# PR5006.net
KiCad netlist of a schematic drawn in EAGLE
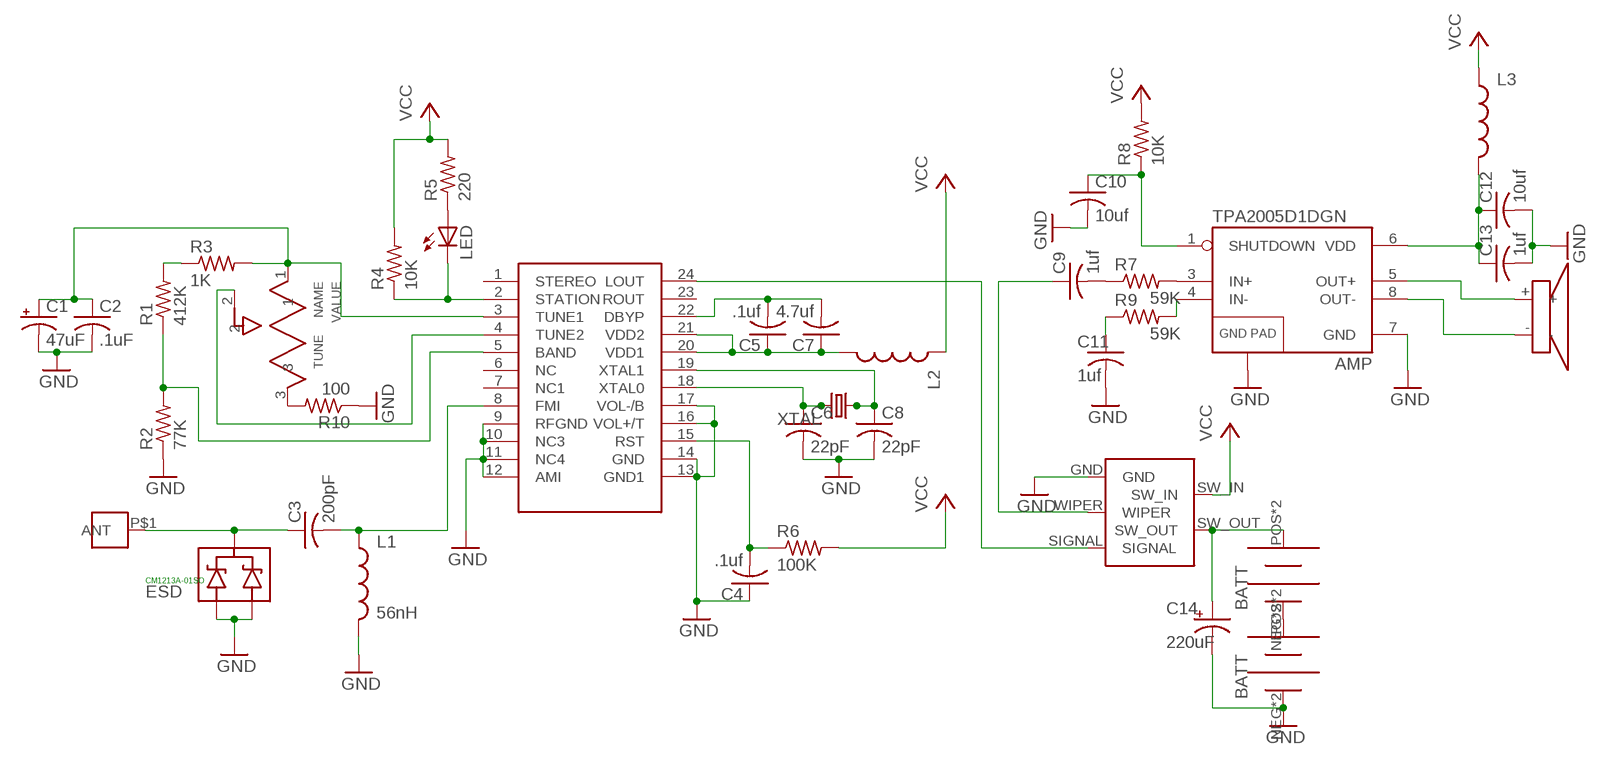
[diagram p0: schematic, sheet 1]

(export (version "E")
  (design (tool "Eeschema 10.0.6"))
  (components
    (comp (ref "AMP")
      (value "TPA2005D1DGN")
      (footprint "eagle-import:POWER-SOP8")
      (libsource (lib "eagle-import") (part "TPA2005D1DGN"))
    )
    (comp (ref "ANT")
      (value "M3_SCREW_POST")
      (footprint "eagle-import:M3_SCREW_POST")
      (libsource (lib "eagle-import") (part "M3_SCREW_POST"))
    )
    (comp (ref "C1")
      (value "47uF")
      (footprint "eagle-import:E2-5")
      (libsource (lib "eagle-import") (part "CPOL-USE2-5"))
    )
    (comp (ref "C2")
      (value ".1uF")
      (footprint "eagle-import:C0603")
      (libsource (lib "eagle-import") (part "C-USC0603"))
    )
    (comp (ref "C3")
      (value "200pF")
      (footprint "eagle-import:C0603")
      (libsource (lib "eagle-import") (part "C-USC0603"))
    )
    (comp (ref "C4")
      (value ".1uf")
      (footprint "eagle-import:C0603")
      (libsource (lib "eagle-import") (part "C-USC0603"))
    )
    (comp (ref "C5")
      (value ".1uf")
      (footprint "eagle-import:C0603")
      (libsource (lib "eagle-import") (part "C-USC0603"))
    )
    (comp (ref "C6")
      (value "22pF")
      (footprint "eagle-import:C0603")
      (libsource (lib "eagle-import") (part "C-USC0603"))
    )
    (comp (ref "C7")
      (value "4.7uf")
      (footprint "eagle-import:C0603")
      (libsource (lib "eagle-import") (part "C-USC0603"))
    )
    (comp (ref "C8")
      (value "22pF")
      (footprint "eagle-import:C0603")
      (libsource (lib "eagle-import") (part "C-USC0603"))
    )
    (comp (ref "C9")
      (value "1uf")
      (footprint "eagle-import:C0603")
      (libsource (lib "eagle-import") (part "C-USC0603"))
    )
    (comp (ref "C10")
      (value "10uf")
      (footprint "eagle-import:C0603")
      (libsource (lib "eagle-import") (part "C-USC0603"))
    )
    (comp (ref "C11")
      (value "1uf")
      (footprint "eagle-import:C0603")
      (libsource (lib "eagle-import") (part "C-USC0603"))
    )
    (comp (ref "C12")
      (value "10uf")
      (footprint "eagle-import:C0603")
      (libsource (lib "eagle-import") (part "C-USC0603"))
    )
    (comp (ref "C13")
      (value "1uf")
      (footprint "eagle-import:C0603")
      (libsource (lib "eagle-import") (part "C-USC0603"))
    )
    (comp (ref "C14")
      (value "220uF")
      (footprint "eagle-import:E2,5-5")
      (libsource (lib "eagle-import") (part "CPOL-USE2.5-5"))
    )
    (comp (ref "ESD")
      (value "CM1213A-01SO")
      (footprint "eagle-import:SOT23-3")
      (libsource (lib "eagle-import") (part "MMBZ27VCLT1"))
    )
    (comp (ref "L1")
      (value "56nH")
      (footprint "eagle-import:0603")
      (libsource (lib "eagle-import") (part "INDUCTOR0603"))
    )
    (comp (ref "L2")
      (value "INDUCTOR0603")
      (footprint "eagle-import:0603")
      (libsource (lib "eagle-import") (part "INDUCTOR0603"))
    )
    (comp (ref "L3")
      (value "INDUCTOR0603")
      (footprint "eagle-import:0603")
      (libsource (lib "eagle-import") (part "INDUCTOR0603"))
    )
    (comp (ref "LED")
      (value "LEDCHIP-LED0603")
      (footprint "eagle-import:CHIP-LED0603")
      (libsource (lib "eagle-import") (part "LEDCHIP-LED0603"))
    )
    (comp (ref "R1")
      (value "412K")
      (footprint "eagle-import:R0603")
      (libsource (lib "eagle-import") (part "R-US_R0603"))
    )
    (comp (ref "R2")
      (value "77K")
      (footprint "eagle-import:R0603")
      (libsource (lib "eagle-import") (part "R-US_R0603"))
    )
    (comp (ref "R3")
      (value "1K")
      (footprint "eagle-import:R0603")
      (libsource (lib "eagle-import") (part "R-US_R0603"))
    )
    (comp (ref "R4")
      (value "10K")
      (footprint "eagle-import:R0603")
      (libsource (lib "eagle-import") (part "R-US_R0603"))
    )
    (comp (ref "R5")
      (value "220")
      (footprint "eagle-import:R0603")
      (libsource (lib "eagle-import") (part "R-US_R0603"))
    )
    (comp (ref "R6")
      (value "100K")
      (footprint "eagle-import:R0603")
      (libsource (lib "eagle-import") (part "R-US_R0603"))
    )
    (comp (ref "R7")
      (value "59K")
      (footprint "eagle-import:R0603")
      (libsource (lib "eagle-import") (part "R-US_R0603"))
    )
    (comp (ref "R8")
      (value "10K")
      (footprint "eagle-import:R0603")
      (libsource (lib "eagle-import") (part "R-US_R0603"))
    )
    (comp (ref "R9")
      (value "59K")
      (footprint "eagle-import:R0603")
      (libsource (lib "eagle-import") (part "R-US_R0603"))
    )
    (comp (ref "R10")
      (value "100")
      (footprint "eagle-import:R0603")
      (libsource (lib "eagle-import") (part "R-US_R0603"))
    )
    (comp (ref "SI4831")
      (value "SI4831-SSOP-24")
      (footprint "eagle-import:SI4831-SSOP-24")
      (libsource (lib "eagle-import") (part "SI4831-SSOP-24"))
    )
    (comp (ref "TUNE")
      (value "TUNE")
      (footprint "eagle-import:64XR_BOURNS_TRIMPOT")
      (libsource (lib "eagle-import") (part "64XR_BOURNS_TRIMPOT"))
    )
    (comp (ref "U$1")
      (value "BK-92_MPD_AA_BATT_CLIP")
      (footprint "eagle-import:BK-92_MPD_AA_BATT_CLIP")
      (libsource (lib "eagle-import") (part "BK-92_MPD_AA_BATT_CLIP"))
    )
    (comp (ref "U$2")
      (value "BK-92_MPD_AA_BATT_CLIP")
      (footprint "eagle-import:BK-92_MPD_AA_BATT_CLIP")
      (libsource (lib "eagle-import") (part "BK-92_MPD_AA_BATT_CLIP"))
    )
    (comp (ref "U$3")
      (value "CE32A_DAYTON_SPKR")
      (footprint "eagle-import:CE32A_DAYTON_SPKR")
      (libsource (lib "eagle-import") (part "CE32A_DAYTON_SPKR"))
    )
    (comp (ref "U$5")
      (value "P170_BOURNS_POT_SW")
      (footprint "eagle-import:P170_BOURNS_POT_SW")
      (libsource (lib "eagle-import") (part "P170_BOURNS_POT_SW"))
    )
    (comp (ref "XTAL")
      (value "CRYSTAL32-SMD")
      (footprint "eagle-import:CRYSTAL-32KHZ-SMD")
      (libsource (lib "eagle-import") (part "CRYSTAL32-SMD"))
    )
  )
  (nets
    (net (code "1") (name "GND") (class "Default")
      (node (ref "AMP") (pin "7") (pinfunction "GND_7") (pintype "power_in"))
      (node (ref "AMP") (pin "9") (pinfunction "GND_9") (pintype "power_in"))
      (node (ref "C1") (pin "-") (pinfunction "-_-") (pintype "passive"))
      (node (ref "C10") (pin "2") (pinfunction "2_2") (pintype "passive"))
      (node (ref "C11") (pin "2") (pinfunction "2_2") (pintype "passive"))
      (node (ref "C12") (pin "2") (pinfunction "2_2") (pintype "passive"))
      (node (ref "C13") (pin "2") (pinfunction "2_2") (pintype "passive"))
      (node (ref "C14") (pin "-") (pinfunction "-_-") (pintype "passive"))
      (node (ref "C2") (pin "2") (pinfunction "2_2") (pintype "passive"))
      (node (ref "C4") (pin "1") (pinfunction "1_1") (pintype "passive"))
      (node (ref "C6") (pin "2") (pinfunction "2_2") (pintype "passive"))
      (node (ref "C8") (pin "2") (pinfunction "2_2") (pintype "passive"))
      (node (ref "ESD") (pin "1") (pinfunction "A1_1") (pintype "passive"))
      (node (ref "ESD") (pin "2") (pinfunction "A2_2") (pintype "passive"))
      (node (ref "L1") (pin "2") (pinfunction "2_2") (pintype "passive"))
      (node (ref "R10") (pin "1") (pinfunction "1_1") (pintype "passive"))
      (node (ref "R2") (pin "1") (pinfunction "1_1") (pintype "passive"))
      (node (ref "SI4831") (pin "10") (pinfunction "NC3_10") (pintype "bidirectional"))
      (node (ref "SI4831") (pin "11") (pinfunction "NC4_11") (pintype "bidirectional"))
      (node (ref "SI4831") (pin "12") (pinfunction "AMI_12") (pintype "bidirectional"))
      (node (ref "SI4831") (pin "13") (pinfunction "GND1_13") (pintype "bidirectional"))
      (node (ref "SI4831") (pin "14") (pinfunction "GND_14") (pintype "bidirectional"))
      (node (ref "SI4831") (pin "16") (pinfunction "VOL+/T_16") (pintype "bidirectional"))
      (node (ref "SI4831") (pin "17") (pinfunction "VOL-/B_17") (pintype "bidirectional"))
      (node (ref "SI4831") (pin "9") (pinfunction "RFGND_9") (pintype "bidirectional"))
      (node (ref "U$2") (pin "NEG") (pinfunction "NEG_NEG") (pintype "bidirectional"))
      (node (ref "U$2") (pin "NEG@2") (pinfunction "NEG_NEG@2") (pintype "bidirectional"))
      (node (ref "U$5") (pin "GND") (pinfunction "GND_GND") (pintype "bidirectional"))
    )
    (net (code "2") (name "Net-(AMP-IN+)") (class "Default")
      (node (ref "AMP") (pin "3") (pinfunction "IN+_3") (pintype "bidirectional"))
      (node (ref "R7") (pin "2") (pinfunction "2_2") (pintype "passive"))
    )
    (net (code "3") (name "Net-(AMP-IN-)") (class "Default")
      (node (ref "AMP") (pin "4") (pinfunction "IN-_4") (pintype "bidirectional"))
      (node (ref "R9") (pin "2") (pinfunction "2_2") (pintype "passive"))
    )
    (net (code "4") (name "Net-(AMP-OUT+)") (class "Default")
      (node (ref "AMP") (pin "5") (pinfunction "OUT+_5") (pintype "bidirectional"))
      (node (ref "U$3") (pin "+") (pinfunction "+_+") (pintype "bidirectional"))
    )
    (net (code "5") (name "Net-(AMP-OUT-)") (class "Default")
      (node (ref "AMP") (pin "8") (pinfunction "OUT-_8") (pintype "bidirectional"))
      (node (ref "U$3") (pin "-") (pinfunction "-_-") (pintype "bidirectional"))
    )
    (net (code "6") (name "Net-(AMP-SHUTDOWN)") (class "Default")
      (node (ref "AMP") (pin "1") (pinfunction "SHUTDOWN_1") (pintype "input"))
      (node (ref "C10") (pin "1") (pinfunction "1_1") (pintype "passive"))
      (node (ref "R8") (pin "1") (pinfunction "1_1") (pintype "passive"))
    )
    (net (code "7") (name "Net-(AMP-VDD)") (class "Default")
      (node (ref "AMP") (pin "6") (pinfunction "VDD_6") (pintype "power_in"))
      (node (ref "C12") (pin "1") (pinfunction "1_1") (pintype "passive"))
      (node (ref "C13") (pin "1") (pinfunction "1_1") (pintype "passive"))
      (node (ref "L3") (pin "2") (pinfunction "2_2") (pintype "passive"))
    )
    (net (code "8") (name "Net-(ANT-ANT)") (class "Default")
      (node (ref "ANT") (pin "P$1") (pinfunction "ANT_P$1") (pintype "bidirectional"))
      (node (ref "C3") (pin "1") (pinfunction "1_1") (pintype "passive"))
      (node (ref "ESD") (pin "3") (pinfunction "C_3") (pintype "passive"))
    )
    (net (code "9") (name "Net-(C9-Pad1)") (class "Default")
      (node (ref "C9") (pin "1") (pinfunction "1_1") (pintype "passive"))
      (node (ref "U$5") (pin "WIPER") (pinfunction "WIPER_WIPER") (pintype "bidirectional"))
    )
    (net (code "10") (name "Net-(C9-Pad2)") (class "Default")
      (node (ref "C9") (pin "2") (pinfunction "2_2") (pintype "passive"))
      (node (ref "R7") (pin "1") (pinfunction "1_1") (pintype "passive"))
    )
    (net (code "11") (name "Net-(C11-Pad1)") (class "Default")
      (node (ref "C11") (pin "1") (pinfunction "1_1") (pintype "passive"))
      (node (ref "R9") (pin "1") (pinfunction "1_1") (pintype "passive"))
    )
    (net (code "12") (name "Net-(C14-Pad+)") (class "Default")
      (node (ref "C14") (pin "+") (pinfunction "+_+") (pintype "passive"))
      (node (ref "U$1") (pin "POS") (pinfunction "POS_POS") (pintype "bidirectional"))
      (node (ref "U$1") (pin "POS@2") (pinfunction "POS_POS@2") (pintype "bidirectional"))
      (node (ref "U$5") (pin "SW_OUT") (pinfunction "SW_OUT_SW_OUT") (pintype "bidirectional"))
    )
    (net (code "13") (name "Net-(LED-PadA)") (class "Default")
      (node (ref "LED") (pin "A") (pinfunction "A_A") (pintype "passive"))
      (node (ref "R5") (pin "1") (pinfunction "1_1") (pintype "passive"))
    )
    (net (code "14") (name "Net-(R1-Pad2)") (class "Default")
      (node (ref "R1") (pin "2") (pinfunction "2_2") (pintype "passive"))
      (node (ref "R3") (pin "1") (pinfunction "1_1") (pintype "passive"))
    )
    (net (code "15") (name "Net-(R10-Pad2)") (class "Default")
      (node (ref "R10") (pin "2") (pinfunction "2_2") (pintype "passive"))
      (node (ref "TUNE") (pin "3") (pinfunction "3_3") (pintype "bidirectional"))
    )
    (net (code "16") (name "Net-(SI4831-BAND)") (class "Default")
      (node (ref "R1") (pin "1") (pinfunction "1_1") (pintype "passive"))
      (node (ref "R2") (pin "2") (pinfunction "2_2") (pintype "passive"))
      (node (ref "SI4831") (pin "5") (pinfunction "BAND_5") (pintype "bidirectional"))
    )
    (net (code "17") (name "Net-(SI4831-DBYP)") (class "Default")
      (node (ref "C5") (pin "2") (pinfunction "2_2") (pintype "passive"))
      (node (ref "C7") (pin "2") (pinfunction "2_2") (pintype "passive"))
      (node (ref "SI4831") (pin "22") (pinfunction "DBYP_22") (pintype "bidirectional"))
    )
    (net (code "18") (name "Net-(SI4831-FMI)") (class "Default")
      (node (ref "C3") (pin "2") (pinfunction "2_2") (pintype "passive"))
      (node (ref "L1") (pin "1") (pinfunction "1_1") (pintype "passive"))
      (node (ref "SI4831") (pin "8") (pinfunction "FMI_8") (pintype "bidirectional"))
    )
    (net (code "19") (name "Net-(SI4831-LOUT)") (class "Default")
      (node (ref "SI4831") (pin "24") (pinfunction "LOUT_24") (pintype "bidirectional"))
      (node (ref "U$5") (pin "SIGNAL") (pinfunction "SIGNAL_SIGNAL") (pintype "bidirectional"))
    )
    (net (code "20") (name "Net-(SI4831-RST)") (class "Default")
      (node (ref "C4") (pin "2") (pinfunction "2_2") (pintype "passive"))
      (node (ref "R6") (pin "1") (pinfunction "1_1") (pintype "passive"))
      (node (ref "SI4831") (pin "15") (pinfunction "RST_15") (pintype "bidirectional"))
    )
    (net (code "21") (name "Net-(SI4831-STATION)") (class "Default")
      (node (ref "LED") (pin "C") (pinfunction "C_C") (pintype "passive"))
      (node (ref "R4") (pin "1") (pinfunction "1_1") (pintype "passive"))
      (node (ref "SI4831") (pin "2") (pinfunction "STATION_2") (pintype "bidirectional"))
    )
    (net (code "22") (name "Net-(SI4831-TUNE1)") (class "Default")
      (node (ref "C1") (pin "+") (pinfunction "+_+") (pintype "passive"))
      (node (ref "C2") (pin "1") (pinfunction "1_1") (pintype "passive"))
      (node (ref "R3") (pin "2") (pinfunction "2_2") (pintype "passive"))
      (node (ref "SI4831") (pin "3") (pinfunction "TUNE1_3") (pintype "bidirectional"))
      (node (ref "TUNE") (pin "1") (pinfunction "1_1") (pintype "bidirectional"))
    )
    (net (code "23") (name "Net-(SI4831-TUNE2)") (class "Default")
      (node (ref "SI4831") (pin "4") (pinfunction "TUNE2_4") (pintype "bidirectional"))
      (node (ref "TUNE") (pin "2") (pinfunction "2_2") (pintype "bidirectional"))
    )
    (net (code "24") (name "Net-(SI4831-VDD1)") (class "Default")
      (node (ref "C5") (pin "1") (pinfunction "1_1") (pintype "passive"))
      (node (ref "C7") (pin "1") (pinfunction "1_1") (pintype "passive"))
      (node (ref "L2") (pin "2") (pinfunction "2_2") (pintype "passive"))
      (node (ref "SI4831") (pin "20") (pinfunction "VDD1_20") (pintype "bidirectional"))
      (node (ref "SI4831") (pin "21") (pinfunction "VDD2_21") (pintype "bidirectional"))
    )
    (net (code "25") (name "Net-(SI4831-XTAL0)") (class "Default")
      (node (ref "C6") (pin "1") (pinfunction "1_1") (pintype "passive"))
      (node (ref "SI4831") (pin "18") (pinfunction "XTAL0_18") (pintype "bidirectional"))
      (node (ref "XTAL") (pin "X2") (pinfunction "2_X2") (pintype "passive"))
    )
    (net (code "26") (name "Net-(SI4831-XTAL1)") (class "Default")
      (node (ref "C8") (pin "1") (pinfunction "1_1") (pintype "passive"))
      (node (ref "SI4831") (pin "19") (pinfunction "XTAL1_19") (pintype "bidirectional"))
      (node (ref "XTAL") (pin "X1") (pinfunction "1_X1") (pintype "passive"))
    )
    (net (code "27") (name "Net-(U$1-NEG-PadNEG@2)") (class "Default")
      (node (ref "U$1") (pin "NEG") (pinfunction "NEG_NEG") (pintype "bidirectional"))
      (node (ref "U$1") (pin "NEG@2") (pinfunction "NEG_NEG@2") (pintype "bidirectional"))
      (node (ref "U$2") (pin "POS") (pinfunction "POS_POS") (pintype "bidirectional"))
      (node (ref "U$2") (pin "POS@2") (pinfunction "POS_POS@2") (pintype "bidirectional"))
    )
    (net (code "28") (name "VCC") (class "Default")
      (node (ref "L2") (pin "1") (pinfunction "1_1") (pintype "passive"))
      (node (ref "L3") (pin "1") (pinfunction "1_1") (pintype "passive"))
      (node (ref "R4") (pin "2") (pinfunction "2_2") (pintype "passive"))
      (node (ref "R5") (pin "2") (pinfunction "2_2") (pintype "passive"))
      (node (ref "R6") (pin "2") (pinfunction "2_2") (pintype "passive"))
      (node (ref "R8") (pin "2") (pinfunction "2_2") (pintype "passive"))
      (node (ref "U$5") (pin "SW_IN") (pinfunction "SW_IN_SW_IN") (pintype "bidirectional"))
    )
    (net (code "29") (name "unconnected-(SI4831-NC-Pad6)") (class "Default")
      (node (ref "SI4831") (pin "6") (pinfunction "NC_6") (pintype "bidirectional"))
    )
    (net (code "30") (name "unconnected-(SI4831-NC1-Pad7)") (class "Default")
      (node (ref "SI4831") (pin "7") (pinfunction "NC1_7") (pintype "bidirectional"))
    )
    (net (code "31") (name "unconnected-(SI4831-ROUT-Pad23)") (class "Default")
      (node (ref "SI4831") (pin "23") (pinfunction "ROUT_23") (pintype "bidirectional"))
    )
    (net (code "32") (name "unconnected-(SI4831-STEREO-Pad1)") (class "Default")
      (node (ref "SI4831") (pin "1") (pinfunction "STEREO_1") (pintype "bidirectional"))
    )
  )
)
